# BV100011_ControlIRS485.net
KiCad netlist of a schematic drawn in Altium Designer
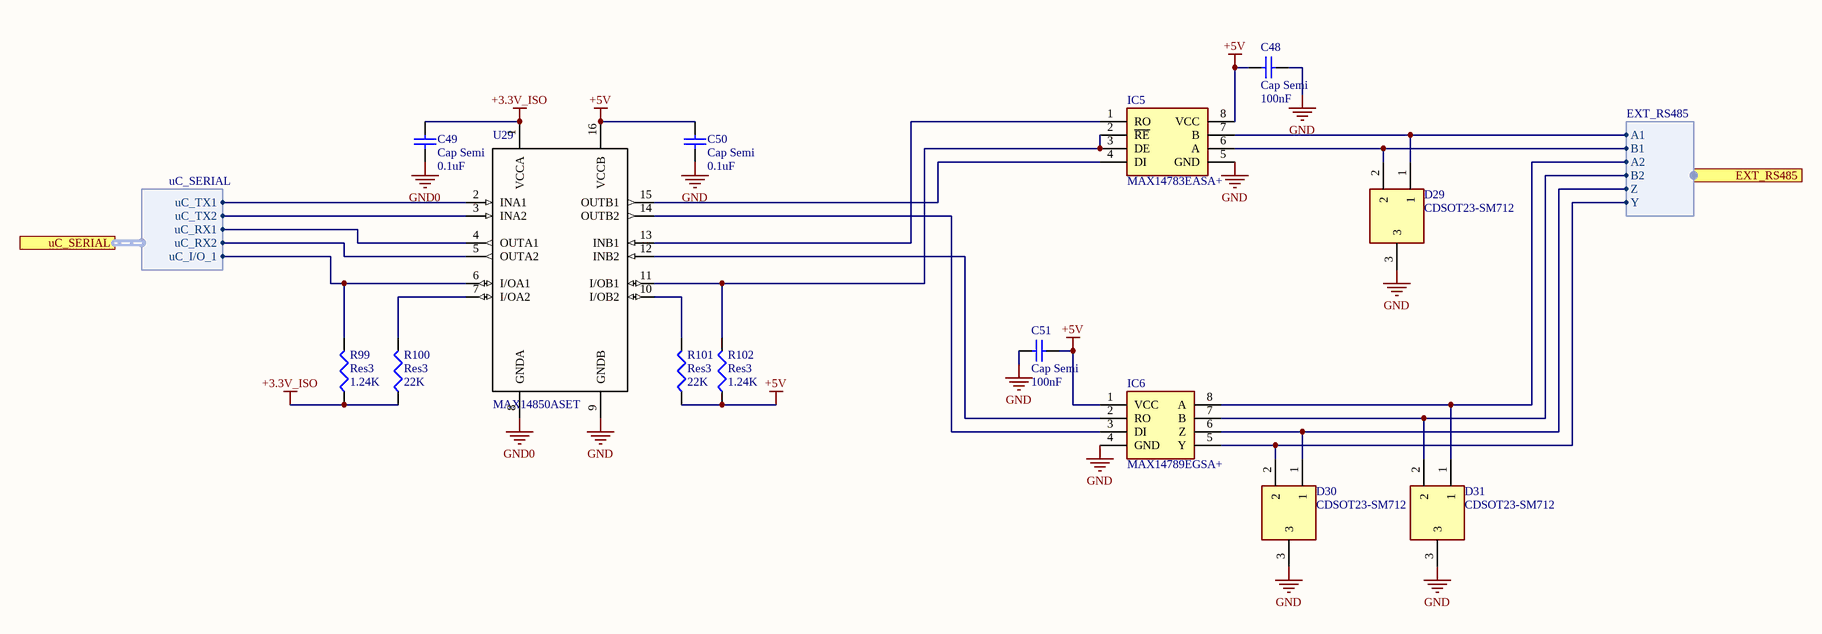
[diagram p0: BV100011_ControlIRS485.SchDoc]

(export (version "E")
  (design (tool "Eeschema 10.0.6"))
  (components
    (comp (ref "C48")
      (value "Cap Semi")
      (footprint "C1206")
      (description "Capacitor (Semiconductor SIM Model)")
      (fields (field (name "ALTIUM_VALUE") "100nF") (field (name "PUBLISHER") "Altium Limited"))
      (libsource (lib "Miscellaneous Devices") (part "Cap Semi"))
    )
    (comp (ref "C49")
      (value "Cap Semi")
      (footprint "C1206")
      (description "Capacitor (Semiconductor SIM Model)")
      (fields (field (name "ALTIUM_VALUE") "0.1uF") (field (name "PUBLISHER") "Altium Limited"))
      (libsource (lib "Miscellaneous Devices") (part "Cap Semi"))
    )
    (comp (ref "C50")
      (value "Cap Semi")
      (footprint "C1206")
      (description "Capacitor (Semiconductor SIM Model)")
      (fields (field (name "ALTIUM_VALUE") "0.1uF") (field (name "PUBLISHER") "Altium Limited"))
      (libsource (lib "Miscellaneous Devices") (part "Cap Semi"))
    )
    (comp (ref "C51")
      (value "Cap Semi")
      (footprint "C1206")
      (description "Capacitor (Semiconductor SIM Model)")
      (fields (field (name "ALTIUM_VALUE") "100nF") (field (name "PUBLISHER") "Altium Limited"))
      (libsource (lib "Miscellaneous Devices") (part "Cap Semi"))
    )
    (comp (ref "D29")
      (value "CDSOT23-SM712")
      (footprint "SOT95P230X117-3N")
      (description "Diode")
      (fields
        (field (name "MOUSER PART NUMBER") "652-CDSOT23-SM712")
        (field (name "RS PART NUMBER") "7673728P")
      )
      (libsource (lib "SM712") (part "CDSOT23-SM712"))
    )
    (comp (ref "D30")
      (value "CDSOT23-SM712")
      (footprint "SOT95P230X117-3N")
      (description "Diode")
      (fields
        (field (name "MOUSER PART NUMBER") "652-CDSOT23-SM712")
        (field (name "RS PART NUMBER") "7673728P")
      )
      (libsource (lib "SM712") (part "CDSOT23-SM712"))
    )
    (comp (ref "D31")
      (value "CDSOT23-SM712")
      (footprint "SOT95P230X117-3N")
      (description "Diode")
      (fields
        (field (name "MOUSER PART NUMBER") "652-CDSOT23-SM712")
        (field (name "RS PART NUMBER") "7673728P")
      )
      (libsource (lib "SM712") (part "CDSOT23-SM712"))
    )
    (comp (ref "IC5")
      (value "MAX14783EASA+")
      (footprint "SOIC127P600X175-8N")
      (description "Integrated Circuit")
      (fields (field (name "MOUSER PART NUMBER") "700-MAX14783EASA+"))
      (libsource (lib "MAX14783EASA+") (part "MAX14783EASA+"))
    )
    (comp (ref "IC6")
      (value "MAX14789EGSA+")
      (footprint "SOIC127P600X175-8N")
      (description "Integrated Circuit")
      (fields (field (name "MOUSER PART NUMBER") "700-MAX14789EGSA+"))
      (libsource (lib "MAX14789EGSA+") (part "MAX14789EGSA+"))
    )
    (comp (ref "R99")
      (value "Res3")
      (footprint "J1-0603")
      (description "Resistor")
      (fields (field (name "ALTIUM_VALUE") "1.24K") (field (name "PUBLISHER") "Altium Limited"))
      (libsource (lib "Miscellaneous Devices") (part "Res3"))
    )
    (comp (ref "R100")
      (value "Res3")
      (footprint "J1-0603")
      (description "Resistor")
      (fields (field (name "ALTIUM_VALUE") "22K") (field (name "PUBLISHER") "Altium Limited"))
      (libsource (lib "Miscellaneous Devices") (part "Res3"))
    )
    (comp (ref "R101")
      (value "Res3")
      (footprint "C1206")
      (description "Resistor")
      (fields (field (name "ALTIUM_VALUE") "22K") (field (name "PUBLISHER") "Altium Limited"))
      (libsource (lib "Miscellaneous Devices") (part "Res3"))
    )
    (comp (ref "R102")
      (value "Res3")
      (footprint "C1206")
      (description "Resistor")
      (fields (field (name "ALTIUM_VALUE") "1.24K") (field (name "PUBLISHER") "Altium Limited"))
      (libsource (lib "Miscellaneous Devices") (part "Res3"))
    )
    (comp (ref "U29")
      (value "MAX14850ASET")
      (footprint "*SOIC127P600X175-16N")
      (description "Digital Isolator, 6-Ch, 30ns, Nsoic-16")
      (fields (field (name "MF") "Maxim Integrated") (field (name "MP") "MAX14850ASE+"))
      (libsource (lib "MAX14850ASET") (part "MAX14850ASET"))
    )
  )
  (nets
    (net (code "3") (name "+3.3V_ISO") (class "Default")
      (node (ref "C49") (pin "1") (pinfunction "1_1") (pintype "passive"))
      (node (ref "R100") (pin "1") (pinfunction "1_1") (pintype "passive"))
      (node (ref "R99") (pin "1") (pinfunction "1_1") (pintype "passive"))
      (node (ref "U29") (pin "1") (pinfunction "VCCA_1") (pintype "power_in"))
    )
    (net (code "4") (name "+5V") (class "Default")
      (node (ref "C48") (pin "1") (pinfunction "1_1") (pintype "passive"))
      (node (ref "C50") (pin "1") (pinfunction "1_1") (pintype "passive"))
      (node (ref "C51") (pin "2") (pinfunction "2_2") (pintype "passive"))
      (node (ref "IC5") (pin "8") (pinfunction "VCC_8") (pintype "passive"))
      (node (ref "IC6") (pin "1") (pinfunction "VCC_1") (pintype "passive"))
      (node (ref "R101") (pin "1") (pinfunction "1_1") (pintype "passive"))
      (node (ref "R102") (pin "1") (pinfunction "1_1") (pintype "passive"))
      (node (ref "U29") (pin "16") (pinfunction "VCCB_16") (pintype "power_in"))
    )
    (net (code "5") (name "/A1") (class "Default")
      (node (ref "D29") (pin "1") (pinfunction "1_1") (pintype "passive"))
      (node (ref "IC5") (pin "7") (pinfunction "B_7") (pintype "passive"))
    )
    (net (code "6") (name "/A2") (class "Default")
      (node (ref "D31") (pin "1") (pinfunction "1_1") (pintype "passive"))
      (node (ref "IC6") (pin "8") (pinfunction "A_8") (pintype "passive"))
    )
    (net (code "7") (name "/B1") (class "Default")
      (node (ref "D29") (pin "2") (pinfunction "2_2") (pintype "passive"))
      (node (ref "IC5") (pin "6") (pinfunction "A_6") (pintype "passive"))
    )
    (net (code "8") (name "/B2") (class "Default")
      (node (ref "D31") (pin "2") (pinfunction "2_2") (pintype "passive"))
      (node (ref "IC6") (pin "7") (pinfunction "B_7") (pintype "passive"))
    )
    (net (code "9") (name "/Y") (class "Default")
      (node (ref "D30") (pin "2") (pinfunction "2_2") (pintype "passive"))
      (node (ref "IC6") (pin "5") (pinfunction "Y_5") (pintype "passive"))
    )
    (net (code "10") (name "/Z") (class "Default")
      (node (ref "D30") (pin "1") (pinfunction "1_1") (pintype "passive"))
      (node (ref "IC6") (pin "6") (pinfunction "Z_6") (pintype "passive"))
    )
    (net (code "11") (name "/uC_I{slash}O_1") (class "Default")
      (node (ref "R99") (pin "2") (pinfunction "2_2") (pintype "passive"))
      (node (ref "U29") (pin "6") (pinfunction "I/OA1_6") (pintype "bidirectional"))
    )
    (net (code "12") (name "/uC_RX1") (class "Default")
      (node (ref "U29") (pin "4") (pinfunction "OUTA1_4") (pintype "output"))
    )
    (net (code "13") (name "/uC_RX2") (class "Default")
      (node (ref "U29") (pin "5") (pinfunction "OUTA2_5") (pintype "output"))
    )
    (net (code "14") (name "/uC_TX1") (class "Default")
      (node (ref "U29") (pin "2") (pinfunction "INA1_2") (pintype "input"))
    )
    (net (code "15") (name "/uC_TX2") (class "Default")
      (node (ref "U29") (pin "3") (pinfunction "INA2_3") (pintype "input"))
    )
    (net (code "18") (name "GND") (class "Default")
      (node (ref "C48") (pin "2") (pinfunction "2_2") (pintype "passive"))
      (node (ref "C50") (pin "2") (pinfunction "2_2") (pintype "passive"))
      (node (ref "C51") (pin "1") (pinfunction "1_1") (pintype "passive"))
      (node (ref "D29") (pin "3") (pinfunction "3_3") (pintype "passive"))
      (node (ref "D30") (pin "3") (pinfunction "3_3") (pintype "passive"))
      (node (ref "D31") (pin "3") (pinfunction "3_3") (pintype "passive"))
      (node (ref "IC5") (pin "5") (pinfunction "GND_5") (pintype "passive"))
      (node (ref "IC6") (pin "4") (pinfunction "GND_4") (pintype "passive"))
      (node (ref "U29") (pin "9") (pinfunction "GNDB_9") (pintype "power_in"))
    )
    (net (code "19") (name "GND0") (class "Default")
      (node (ref "C49") (pin "2") (pinfunction "2_2") (pintype "passive"))
      (node (ref "U29") (pin "8") (pinfunction "GNDA_8") (pintype "power_in"))
    )
    (net (code "20") (name "Net-(IC5-DE)") (class "Default")
      (node (ref "IC5") (pin "2") (pinfunction "~{RE}_2") (pintype "passive"))
      (node (ref "IC5") (pin "3") (pinfunction "DE_3") (pintype "passive"))
      (node (ref "R102") (pin "2") (pinfunction "2_2") (pintype "passive"))
      (node (ref "U29") (pin "11") (pinfunction "I/OB1_11") (pintype "bidirectional"))
    )
    (net (code "21") (name "Net-(IC5-DI)") (class "Default")
      (node (ref "IC5") (pin "4") (pinfunction "DI_4") (pintype "passive"))
      (node (ref "U29") (pin "15") (pinfunction "OUTB1_15") (pintype "output"))
    )
    (net (code "22") (name "Net-(IC5-RO)") (class "Default")
      (node (ref "IC5") (pin "1") (pinfunction "RO_1") (pintype "passive"))
      (node (ref "U29") (pin "13") (pinfunction "INB1_13") (pintype "input"))
    )
    (net (code "23") (name "Net-(IC6-DI)") (class "Default")
      (node (ref "IC6") (pin "3") (pinfunction "DI_3") (pintype "passive"))
      (node (ref "U29") (pin "14") (pinfunction "OUTB2_14") (pintype "output"))
    )
    (net (code "24") (name "Net-(IC6-RO)") (class "Default")
      (node (ref "IC6") (pin "2") (pinfunction "RO_2") (pintype "passive"))
      (node (ref "U29") (pin "12") (pinfunction "INB2_12") (pintype "input"))
    )
    (net (code "25") (name "Net-(U29-I{slash}OA2)") (class "Default")
      (node (ref "R100") (pin "2") (pinfunction "2_2") (pintype "passive"))
      (node (ref "U29") (pin "7") (pinfunction "I/OA2_7") (pintype "bidirectional"))
    )
    (net (code "26") (name "Net-(U29-I{slash}OB2)") (class "Default")
      (node (ref "R101") (pin "2") (pinfunction "2_2") (pintype "passive"))
      (node (ref "U29") (pin "10") (pinfunction "I/OB2_10") (pintype "bidirectional"))
    )
  )
)
